# IL01.net
KiCad netlist of a schematic drawn in EAGLE
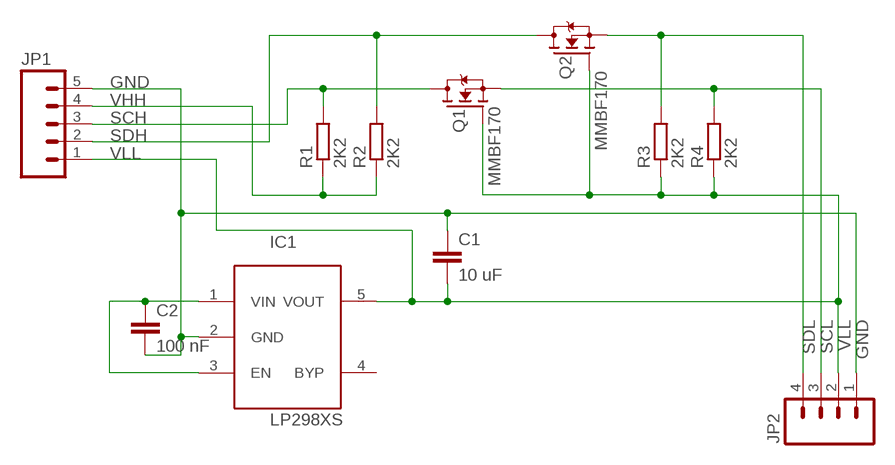
[diagram p0: schematic, sheet 1]

(export (version "E")
  (design (tool "Eeschema 10.0.6"))
  (components
    (comp (ref "C1")
      (value "10 uF")
      (footprint "eagle-import:C1206")
      (libsource (lib "eagle-import") (part "C-EUC1206"))
    )
    (comp (ref "C2")
      (value "100 nF")
      (footprint "eagle-import:C0805")
      (libsource (lib "eagle-import") (part "C-EUC0805"))
    )
    (comp (ref "IC1")
      (value "LP298XS")
      (footprint "eagle-import:SOT23-5L")
      (libsource (lib "eagle-import") (part "LP298XS"))
    )
    (comp (ref "JP1")
      (value "M05PTH")
      (footprint "eagle-import:1X05")
      (libsource (lib "eagle-import") (part "M05PTH"))
    )
    (comp (ref "JP2")
      (value "M04PTH")
      (footprint "eagle-import:1X04")
      (libsource (lib "eagle-import") (part "M04PTH"))
    )
    (comp (ref "Q1")
      (value "MMBF170")
      (footprint "eagle-import:SOT-23")
      (libsource (lib "eagle-import") (part "TRANSISTOR_FET_BS170-SOT-23"))
    )
    (comp (ref "Q2")
      (value "MMBF170")
      (footprint "eagle-import:SOT-23")
      (libsource (lib "eagle-import") (part "TRANSISTOR_FET_BS170-SOT-23"))
    )
    (comp (ref "R1")
      (value "2K2")
      (footprint "eagle-import:R0603")
      (libsource (lib "eagle-import") (part "R-EU_R0603"))
    )
    (comp (ref "R2")
      (value "2K2")
      (footprint "eagle-import:R0603")
      (libsource (lib "eagle-import") (part "R-EU_R0603"))
    )
    (comp (ref "R3")
      (value "2K2")
      (footprint "eagle-import:R0603")
      (libsource (lib "eagle-import") (part "R-EU_R0603"))
    )
    (comp (ref "R4")
      (value "2K2")
      (footprint "eagle-import:R0603")
      (libsource (lib "eagle-import") (part "R-EU_R0603"))
    )
  )
  (nets
    (net (code "1") (name "/GND") (class "Default")
      (node (ref "C1") (pin "1") (pinfunction "1_1") (pintype "passive"))
      (node (ref "C2") (pin "2") (pinfunction "2_2") (pintype "passive"))
      (node (ref "IC1") (pin "2") (pinfunction "GND_2") (pintype "bidirectional"))
      (node (ref "JP1") (pin "5") (pinfunction "5_5") (pintype "passive"))
      (node (ref "JP2") (pin "1") (pinfunction "1_1") (pintype "passive"))
    )
    (net (code "2") (name "/SCH") (class "Default")
      (node (ref "JP1") (pin "3") (pinfunction "3_3") (pintype "passive"))
      (node (ref "Q1") (pin "3") (pinfunction "D_3") (pintype "passive"))
      (node (ref "R1") (pin "2") (pinfunction "2_2") (pintype "passive"))
    )
    (net (code "3") (name "/SCL") (class "Default")
      (node (ref "JP2") (pin "4") (pinfunction "4_4") (pintype "passive"))
      (node (ref "Q2") (pin "2") (pinfunction "S_2") (pintype "passive"))
      (node (ref "R3") (pin "2") (pinfunction "2_2") (pintype "passive"))
    )
    (net (code "4") (name "/SDH") (class "Default")
      (node (ref "JP1") (pin "2") (pinfunction "2_2") (pintype "passive"))
      (node (ref "Q2") (pin "3") (pinfunction "D_3") (pintype "passive"))
      (node (ref "R2") (pin "2") (pinfunction "2_2") (pintype "passive"))
    )
    (net (code "5") (name "/SDL") (class "Default")
      (node (ref "JP2") (pin "3") (pinfunction "3_3") (pintype "passive"))
      (node (ref "Q1") (pin "2") (pinfunction "S_2") (pintype "passive"))
      (node (ref "R4") (pin "2") (pinfunction "2_2") (pintype "passive"))
    )
    (net (code "6") (name "/VHH") (class "Default")
      (node (ref "C2") (pin "1") (pinfunction "1_1") (pintype "passive"))
      (node (ref "IC1") (pin "1") (pinfunction "VIN_1") (pintype "bidirectional"))
      (node (ref "IC1") (pin "3") (pinfunction "EN_3") (pintype "bidirectional"))
      (node (ref "JP1") (pin "4") (pinfunction "4_4") (pintype "passive"))
      (node (ref "R1") (pin "1") (pinfunction "1_1") (pintype "passive"))
      (node (ref "R2") (pin "1") (pinfunction "1_1") (pintype "passive"))
    )
    (net (code "7") (name "/VLL") (class "Default")
      (node (ref "C1") (pin "2") (pinfunction "2_2") (pintype "passive"))
      (node (ref "IC1") (pin "5") (pinfunction "VOUT_5") (pintype "bidirectional"))
      (node (ref "JP1") (pin "1") (pinfunction "1_1") (pintype "passive"))
      (node (ref "JP2") (pin "2") (pinfunction "2_2") (pintype "passive"))
      (node (ref "Q1") (pin "1") (pinfunction "G_1") (pintype "passive"))
      (node (ref "Q2") (pin "1") (pinfunction "G_1") (pintype "passive"))
      (node (ref "R3") (pin "1") (pinfunction "1_1") (pintype "passive"))
      (node (ref "R4") (pin "1") (pinfunction "1_1") (pintype "passive"))
    )
    (net (code "8") (name "unconnected-(IC1-BYP-Pad4)") (class "Default")
      (node (ref "IC1") (pin "4") (pinfunction "BYP_4") (pintype "bidirectional"))
    )
  )
)
